# 1605_lora_ES920.net
KiCad netlist of a schematic drawn in EAGLE
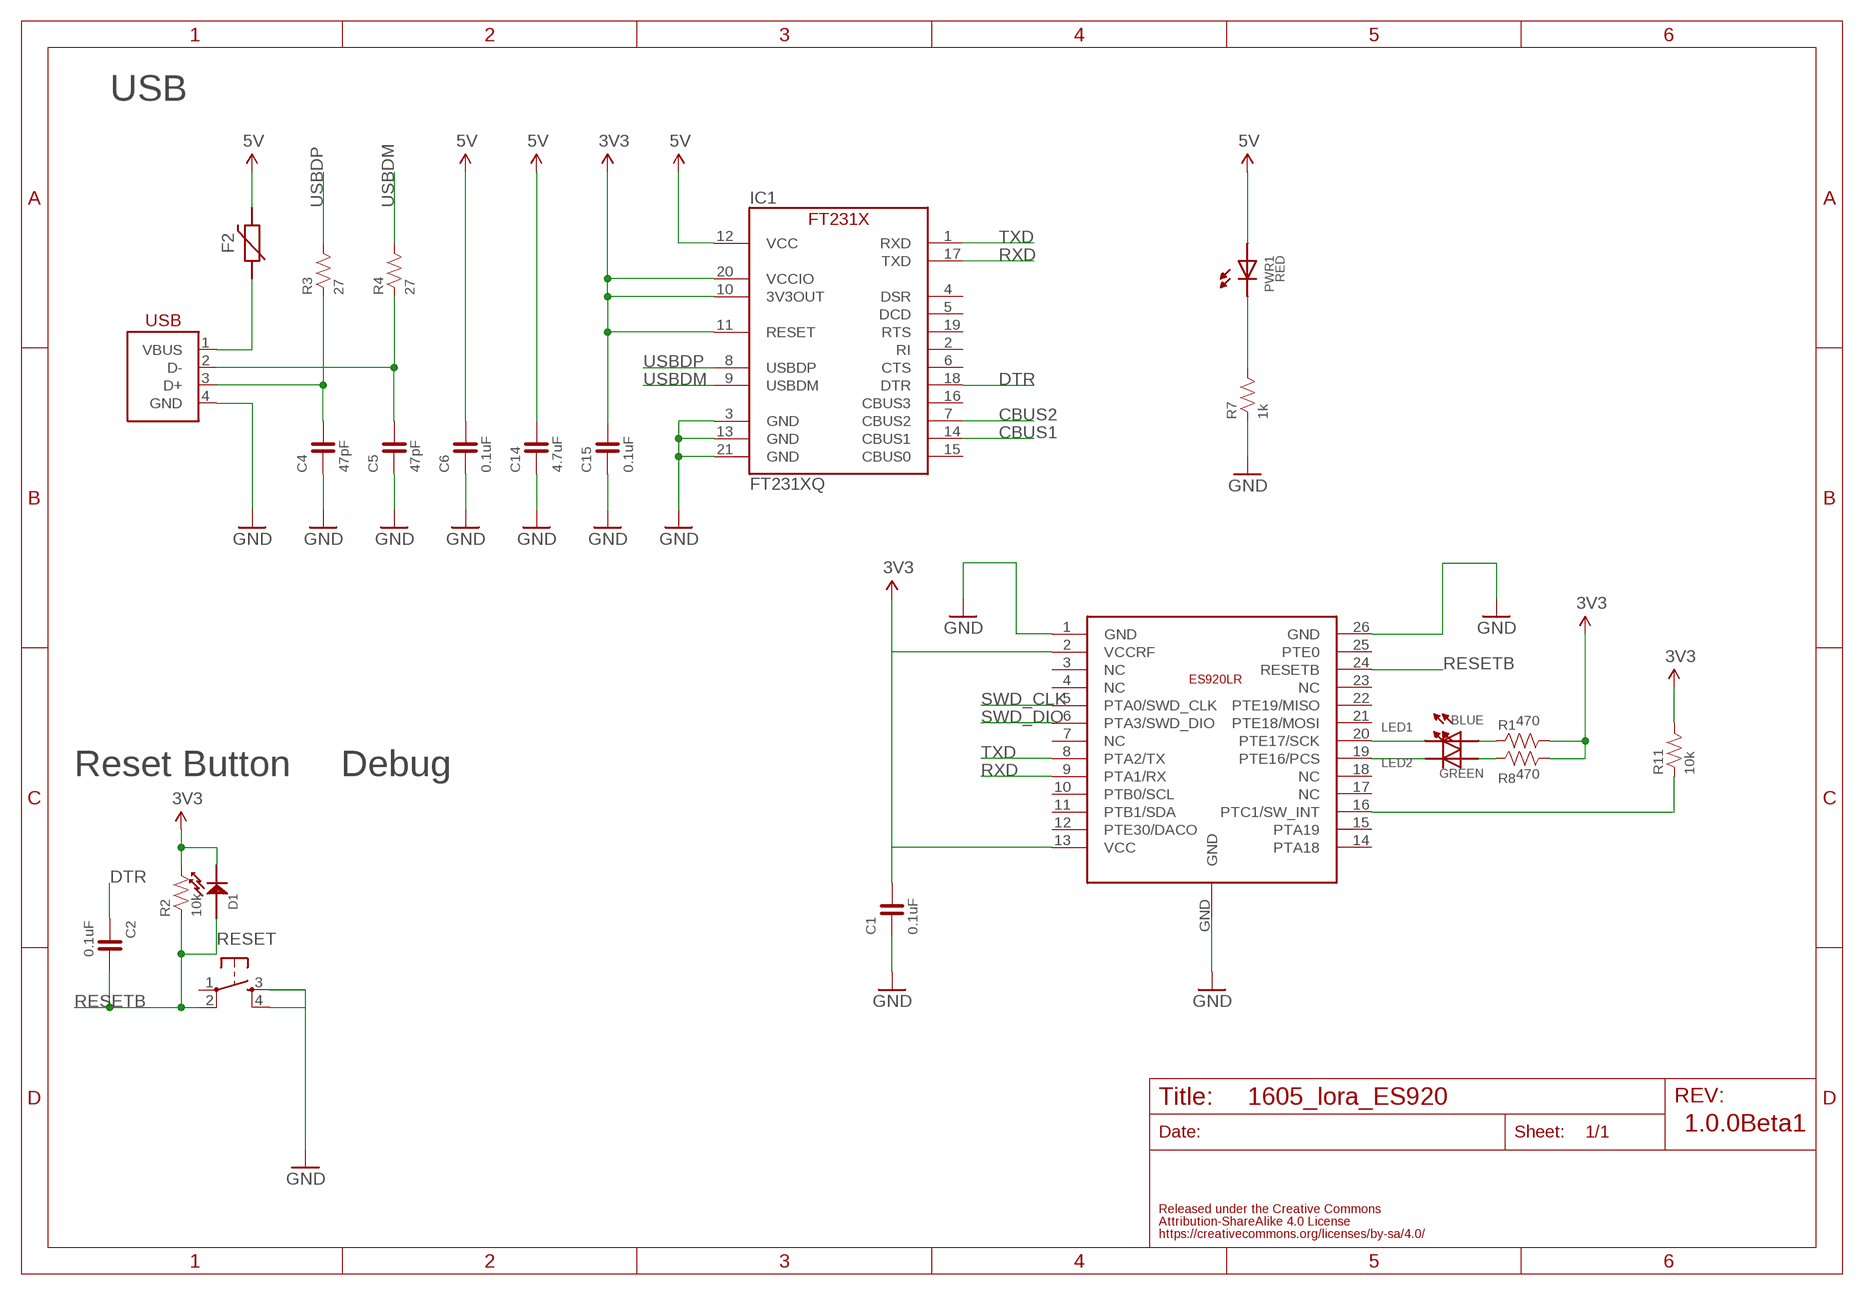
[diagram p0: schematic, sheet 1]

(export (version "E")
  (design (tool "Eeschema 10.0.6"))
  (components
    (comp (ref "C1")
      (value "0.1uF")
      (footprint "eagle-import:0603-NARROW")
      (libsource (lib "eagle-import") (part "CAPACITOR-0603_NARROW"))
    )
    (comp (ref "C2")
      (value "0.1uF")
      (footprint "eagle-import:0603-NARROW")
      (libsource (lib "eagle-import") (part "CAPACITOR-0603_NARROW"))
    )
    (comp (ref "C4")
      (value "47pF")
      (footprint "eagle-import:0603-NARROW")
      (libsource (lib "eagle-import") (part "CAPACITOR-0603_NARROW"))
    )
    (comp (ref "C5")
      (value "47pF")
      (footprint "eagle-import:0603-NARROW")
      (libsource (lib "eagle-import") (part "CAPACITOR-0603_NARROW"))
    )
    (comp (ref "C6")
      (value "0.1uF")
      (footprint "eagle-import:0603-NARROW")
      (libsource (lib "eagle-import") (part "CAPACITOR-0603_NARROW"))
    )
    (comp (ref "C14")
      (value "4.7uF")
      (footprint "eagle-import:0603-NARROW")
      (libsource (lib "eagle-import") (part "CAPACITOR-0603_NARROW"))
    )
    (comp (ref "C15")
      (value "0.1uF")
      (footprint "eagle-import:0603-NARROW")
      (libsource (lib "eagle-import") (part "CAPACITOR-0603_NARROW"))
    )
    (comp (ref "D1")
      (value "DIODE0603")
      (footprint "eagle-import:0603")
      (libsource (lib "eagle-import") (part "DIODE0603"))
    )
    (comp (ref "F2")
      (value "POLYSWITCH")
      (footprint "eagle-import:NANOSMDC035F")
      (libsource (lib "eagle-import") (part "POLYSWITCH"))
    )
    (comp (ref "IC1")
      (value "FT231XQ")
      (footprint "eagle-import:QFN-20_FT231X")
      (libsource (lib "eagle-import") (part "FT231XQ"))
    )
    (comp (ref "LED1")
      (value "BLUE")
      (footprint "eagle-import:0603")
      (libsource (lib "eagle-import") (part "LED-0603"))
    )
    (comp (ref "LED2")
      (value "GREEN")
      (footprint "eagle-import:0603")
      (libsource (lib "eagle-import") (part "LED-0603"))
    )
    (comp (ref "PWR1")
      (value "RED")
      (footprint "eagle-import:0603-NARROW")
      (libsource (lib "eagle-import") (part "LED-0603-NARROW"))
    )
    (comp (ref "R1")
      (value "470")
      (footprint "eagle-import:0603-NARROW")
      (libsource (lib "eagle-import") (part "RESISTOR-0603-NARROW"))
    )
    (comp (ref "R2")
      (value "10k")
      (footprint "eagle-import:0603-NARROW")
      (libsource (lib "eagle-import") (part "RESISTOR-0603-NARROW"))
    )
    (comp (ref "R3")
      (value "27")
      (footprint "eagle-import:0603-NARROW")
      (libsource (lib "eagle-import") (part "RESISTOR-0603-NARROW"))
    )
    (comp (ref "R4")
      (value "27")
      (footprint "eagle-import:0603-NARROW")
      (libsource (lib "eagle-import") (part "RESISTOR-0603-NARROW"))
    )
    (comp (ref "R7")
      (value "1k")
      (footprint "eagle-import:0603-NARROW")
      (libsource (lib "eagle-import") (part "RESISTOR-0603-NARROW"))
    )
    (comp (ref "R8")
      (value "470")
      (footprint "eagle-import:0603-NARROW")
      (libsource (lib "eagle-import") (part "RESISTOR-0603-NARROW"))
    )
    (comp (ref "R11")
      (value "10k")
      (footprint "eagle-import:0603-NARROW")
      (libsource (lib "eagle-import") (part "RESISTOR-0603-NARROW"))
    )
    (comp (ref "RESET")
      (value "TACT-SWITCH-SMD_KMR2")
      (footprint "eagle-import:KMR2")
      (libsource (lib "eagle-import") (part "TACT-SWITCH-SMD_KMR2"))
    )
    (comp (ref "U$4")
      (value "ES920LR")
      (footprint "eagle-import:ES920LR")
      (libsource (lib "eagle-import") (part "ES920LR"))
    )
    (comp (ref "USB1")
      (value "USB-B_PTH")
      (footprint "eagle-import:USB-4AF103BS")
      (libsource (lib "eagle-import") (part "USB-B_PTH"))
    )
  )
  (nets
    (net (code "1") (name "/CBUS1") (class "Default")
      (node (ref "IC1") (pin "14") (pinfunction "CBUS1_14") (pintype "bidirectional"))
    )
    (net (code "2") (name "/CBUS2") (class "Default")
      (node (ref "IC1") (pin "7") (pinfunction "CBUS2_7") (pintype "bidirectional"))
    )
    (net (code "3") (name "/DTR") (class "Default")
      (node (ref "C2") (pin "1") (pinfunction "1_1") (pintype "passive"))
      (node (ref "IC1") (pin "18") (pinfunction "DTR_18") (pintype "bidirectional"))
    )
    (net (code "4") (name "/RESETB") (class "Default")
      (node (ref "C2") (pin "2") (pinfunction "2_2") (pintype "passive"))
      (node (ref "D1") (pin "ANODE") (pinfunction "ANODE_ANODE") (pintype "bidirectional"))
      (node (ref "R2") (pin "1") (pinfunction "1_1") (pintype "bidirectional"))
      (node (ref "RESET") (pin "2") (pinfunction "2_2") (pintype "passive"))
      (node (ref "U$4") (pin "24") (pinfunction "RESETB_24") (pintype "bidirectional"))
    )
    (net (code "5") (name "/RXD") (class "Default")
      (node (ref "IC1") (pin "17") (pinfunction "TXD_17") (pintype "bidirectional"))
      (node (ref "U$4") (pin "9") (pinfunction "PTA1/RX_9") (pintype "bidirectional"))
    )
    (net (code "6") (name "/SWD_CLK") (class "Default")
      (node (ref "U$4") (pin "5") (pinfunction "PTA0/SWD_CLK_5") (pintype "bidirectional"))
    )
    (net (code "7") (name "/SWD_DIO") (class "Default")
      (node (ref "U$4") (pin "6") (pinfunction "PTA3/SWD_DIO_6") (pintype "bidirectional"))
    )
    (net (code "8") (name "/TXD") (class "Default")
      (node (ref "IC1") (pin "1") (pinfunction "RXD_1") (pintype "bidirectional"))
      (node (ref "U$4") (pin "8") (pinfunction "PTA2/TX_8") (pintype "bidirectional"))
    )
    (net (code "9") (name "/USBDM") (class "Default")
      (node (ref "IC1") (pin "9") (pinfunction "USBDM_9") (pintype "bidirectional"))
      (node (ref "R4") (pin "2") (pinfunction "2_2") (pintype "bidirectional"))
    )
    (net (code "10") (name "/USBDP") (class "Default")
      (node (ref "IC1") (pin "8") (pinfunction "USBDP_8") (pintype "bidirectional"))
      (node (ref "R3") (pin "2") (pinfunction "2_2") (pintype "bidirectional"))
    )
    (net (code "11") (name "3V3") (class "Default")
      (node (ref "C1") (pin "2") (pinfunction "2_2") (pintype "passive"))
      (node (ref "C15") (pin "2") (pinfunction "2_2") (pintype "passive"))
      (node (ref "D1") (pin "CATHODE") (pinfunction "CATHODE_CATHODE") (pintype "bidirectional"))
      (node (ref "IC1") (pin "10") (pinfunction "3V3OUT_10") (pintype "bidirectional"))
      (node (ref "IC1") (pin "11") (pinfunction "RESET_11") (pintype "bidirectional"))
      (node (ref "IC1") (pin "20") (pinfunction "VCCIO_20") (pintype "bidirectional"))
      (node (ref "R1") (pin "2") (pinfunction "2_2") (pintype "bidirectional"))
      (node (ref "R11") (pin "2") (pinfunction "2_2") (pintype "bidirectional"))
      (node (ref "R2") (pin "2") (pinfunction "2_2") (pintype "bidirectional"))
      (node (ref "R8") (pin "2") (pinfunction "2_2") (pintype "bidirectional"))
      (node (ref "U$4") (pin "13") (pinfunction "VCC_13") (pintype "bidirectional"))
      (node (ref "U$4") (pin "2") (pinfunction "VCCRF_2") (pintype "bidirectional"))
    )
    (net (code "12") (name "5V") (class "Default")
      (node (ref "C14") (pin "2") (pinfunction "2_2") (pintype "passive"))
      (node (ref "C6") (pin "2") (pinfunction "2_2") (pintype "passive"))
      (node (ref "F2") (pin "2") (pinfunction "2_2") (pintype "bidirectional"))
      (node (ref "IC1") (pin "12") (pinfunction "VCC_12") (pintype "bidirectional"))
      (node (ref "PWR1") (pin "ANODE") (pinfunction "ANODE_ANODE") (pintype "passive"))
    )
    (net (code "13") (name "GND") (class "Default")
      (node (ref "C1") (pin "1") (pinfunction "1_1") (pintype "passive"))
      (node (ref "C14") (pin "1") (pinfunction "1_1") (pintype "passive"))
      (node (ref "C15") (pin "1") (pinfunction "1_1") (pintype "passive"))
      (node (ref "C4") (pin "1") (pinfunction "1_1") (pintype "passive"))
      (node (ref "C5") (pin "1") (pinfunction "1_1") (pintype "passive"))
      (node (ref "C6") (pin "1") (pinfunction "1_1") (pintype "passive"))
      (node (ref "IC1") (pin "13") (pinfunction "GND_13") (pintype "bidirectional"))
      (node (ref "IC1") (pin "21") (pinfunction "GND_21") (pintype "bidirectional"))
      (node (ref "IC1") (pin "3") (pinfunction "GND_3") (pintype "bidirectional"))
      (node (ref "R7") (pin "1") (pinfunction "1_1") (pintype "bidirectional"))
      (node (ref "RESET") (pin "3") (pinfunction "3_3") (pintype "passive"))
      (node (ref "RESET") (pin "4") (pinfunction "4_4") (pintype "passive"))
      (node (ref "U$4") (pin "1") (pinfunction "GND_1") (pintype "bidirectional"))
      (node (ref "U$4") (pin "26") (pinfunction "GND_26") (pintype "bidirectional"))
      (node (ref "U$4") (pin "GND") (pinfunction "GND_GND") (pintype "bidirectional"))
      (node (ref "USB1") (pin "4") (pinfunction "GND_4") (pintype "bidirectional"))
    )
    (net (code "14") (name "Net-(LED1-PadANODE)") (class "Default")
      (node (ref "LED1") (pin "ANODE") (pinfunction "ANODE_ANODE") (pintype "passive"))
      (node (ref "R1") (pin "1") (pinfunction "1_1") (pintype "bidirectional"))
    )
    (net (code "15") (name "Net-(LED2-PadANODE)") (class "Default")
      (node (ref "LED2") (pin "ANODE") (pinfunction "ANODE_ANODE") (pintype "passive"))
      (node (ref "R8") (pin "1") (pinfunction "1_1") (pintype "bidirectional"))
    )
    (net (code "16") (name "Net-(PWR1-PadCATHODE)") (class "Default")
      (node (ref "PWR1") (pin "CATHODE") (pinfunction "CATHODE_CATHODE") (pintype "passive"))
      (node (ref "R7") (pin "2") (pinfunction "2_2") (pintype "bidirectional"))
    )
    (net (code "17") (name "Net-(U$4-PTC1{slash}SW_INT)") (class "Default")
      (node (ref "R11") (pin "1") (pinfunction "1_1") (pintype "bidirectional"))
      (node (ref "U$4") (pin "16") (pinfunction "PTC1/SW_INT_16") (pintype "bidirectional"))
    )
    (net (code "18") (name "Net-(U$4-PTE16{slash}PCS)") (class "Default")
      (node (ref "LED2") (pin "CATHODE") (pinfunction "CATHODE_CATHODE") (pintype "passive"))
      (node (ref "U$4") (pin "19") (pinfunction "PTE16/PCS_19") (pintype "bidirectional"))
    )
    (net (code "19") (name "Net-(U$4-PTE17{slash}SCK)") (class "Default")
      (node (ref "LED1") (pin "CATHODE") (pinfunction "CATHODE_CATHODE") (pintype "passive"))
      (node (ref "U$4") (pin "20") (pinfunction "PTE17/SCK_20") (pintype "bidirectional"))
    )
    (net (code "20") (name "Net-(USB1-D+)") (class "Default")
      (node (ref "C4") (pin "2") (pinfunction "2_2") (pintype "passive"))
      (node (ref "R3") (pin "1") (pinfunction "1_1") (pintype "bidirectional"))
      (node (ref "USB1") (pin "3") (pinfunction "D+_3") (pintype "bidirectional"))
    )
    (net (code "21") (name "Net-(USB1-D-)") (class "Default")
      (node (ref "C5") (pin "2") (pinfunction "2_2") (pintype "passive"))
      (node (ref "R4") (pin "1") (pinfunction "1_1") (pintype "bidirectional"))
      (node (ref "USB1") (pin "2") (pinfunction "D-_2") (pintype "bidirectional"))
    )
    (net (code "22") (name "Net-(USB1-VBUS)") (class "Default")
      (node (ref "F2") (pin "1") (pinfunction "1_1") (pintype "bidirectional"))
      (node (ref "USB1") (pin "1") (pinfunction "VBUS_1") (pintype "bidirectional"))
    )
    (net (code "23") (name "unconnected-(IC1-CBUS0-Pad15)") (class "Default")
      (node (ref "IC1") (pin "15") (pinfunction "CBUS0_15") (pintype "bidirectional"))
    )
    (net (code "24") (name "unconnected-(IC1-CBUS3-Pad16)") (class "Default")
      (node (ref "IC1") (pin "16") (pinfunction "CBUS3_16") (pintype "bidirectional"))
    )
    (net (code "25") (name "unconnected-(IC1-CTS-Pad6)") (class "Default")
      (node (ref "IC1") (pin "6") (pinfunction "CTS_6") (pintype "bidirectional"))
    )
    (net (code "26") (name "unconnected-(IC1-DCD-Pad5)") (class "Default")
      (node (ref "IC1") (pin "5") (pinfunction "DCD_5") (pintype "bidirectional"))
    )
    (net (code "27") (name "unconnected-(IC1-DSR-Pad4)") (class "Default")
      (node (ref "IC1") (pin "4") (pinfunction "DSR_4") (pintype "bidirectional"))
    )
    (net (code "28") (name "unconnected-(IC1-RI-Pad2)") (class "Default")
      (node (ref "IC1") (pin "2") (pinfunction "RI_2") (pintype "bidirectional"))
    )
    (net (code "29") (name "unconnected-(IC1-RTS-Pad19)") (class "Default")
      (node (ref "IC1") (pin "19") (pinfunction "RTS_19") (pintype "bidirectional"))
    )
    (net (code "30") (name "unconnected-(RESET-Pad1)") (class "Default")
      (node (ref "RESET") (pin "1") (pinfunction "1_1") (pintype "passive"))
    )
    (net (code "31") (name "unconnected-(U$4-NC-Pad3)") (class "Default")
      (node (ref "U$4") (pin "3") (pinfunction "NC_3") (pintype "bidirectional"))
    )
    (net (code "32") (name "unconnected-(U$4-NC-Pad4)") (class "Default")
      (node (ref "U$4") (pin "4") (pinfunction "NC_4") (pintype "bidirectional"))
    )
    (net (code "33") (name "unconnected-(U$4-NC-Pad7)") (class "Default")
      (node (ref "U$4") (pin "7") (pinfunction "NC_7") (pintype "bidirectional"))
    )
    (net (code "34") (name "unconnected-(U$4-NC-Pad17)") (class "Default")
      (node (ref "U$4") (pin "17") (pinfunction "NC_17") (pintype "bidirectional"))
    )
    (net (code "35") (name "unconnected-(U$4-NC-Pad18)") (class "Default")
      (node (ref "U$4") (pin "18") (pinfunction "NC_18") (pintype "bidirectional"))
    )
    (net (code "36") (name "unconnected-(U$4-NC-Pad23)") (class "Default")
      (node (ref "U$4") (pin "23") (pinfunction "NC_23") (pintype "bidirectional"))
    )
    (net (code "37") (name "unconnected-(U$4-PTA18-Pad14)") (class "Default")
      (node (ref "U$4") (pin "14") (pinfunction "PTA18_14") (pintype "bidirectional"))
    )
    (net (code "38") (name "unconnected-(U$4-PTA19-Pad15)") (class "Default")
      (node (ref "U$4") (pin "15") (pinfunction "PTA19_15") (pintype "bidirectional"))
    )
    (net (code "39") (name "unconnected-(U$4-PTB0{slash}SCL-Pad10)") (class "Default")
      (node (ref "U$4") (pin "10") (pinfunction "PTB0/SCL_10") (pintype "bidirectional"))
    )
    (net (code "40") (name "unconnected-(U$4-PTB1{slash}SDA-Pad11)") (class "Default")
      (node (ref "U$4") (pin "11") (pinfunction "PTB1/SDA_11") (pintype "bidirectional"))
    )
    (net (code "41") (name "unconnected-(U$4-PTE0-Pad25)") (class "Default")
      (node (ref "U$4") (pin "25") (pinfunction "PTE0_25") (pintype "bidirectional"))
    )
    (net (code "42") (name "unconnected-(U$4-PTE18{slash}MOSI-Pad21)") (class "Default")
      (node (ref "U$4") (pin "21") (pinfunction "PTE18/MOSI_21") (pintype "bidirectional"))
    )
    (net (code "43") (name "unconnected-(U$4-PTE19{slash}MISO-Pad22)") (class "Default")
      (node (ref "U$4") (pin "22") (pinfunction "PTE19/MISO_22") (pintype "bidirectional"))
    )
    (net (code "44") (name "unconnected-(U$4-PTE30{slash}DACO-Pad12)") (class "Default")
      (node (ref "U$4") (pin "12") (pinfunction "PTE30/DACO_12") (pintype "bidirectional"))
    )
  )
)
